# Crpto01JTAG.net
KiCad netlist of a schematic drawn in Altium Designer
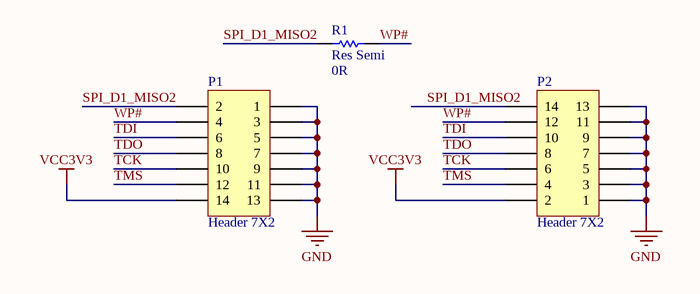
[diagram p0: Crpto01JTAG.SchDoc]

(export (version "E")
  (design (tool "Eeschema 10.0.6"))
  (components
    (comp (ref "P1")
      (value "Header 7X2")
      (footprint "JTAG_WM9059CT-ND")
      (description "Header, 7-Pin, Dual row")
      (fields (field (name "PUBLISHER") "Altium Limited"))
      (libsource (lib "") (part "Header 7X2_1"))
    )
    (comp (ref "P2")
      (value "Header 7X2")
      (footprint "2x7_2.0mm_Header")
      (description "Header, 7-Pin, Dual row")
      (fields (field (name "PUBLISHER") "Altium Limited"))
      (libsource (lib "Miscellaneous Connectors") (part "Header 7X2"))
    )
    (comp (ref "R1")
      (value "Res Semi")
      (footprint "0402")
      (description "Semiconductor Resistor")
      (fields (field (name "ALTIUM_VALUE") "0R") (field (name "PUBLISHER") "Altium Limited"))
      (libsource (lib "Miscellaneous Devices") (part "Res Semi"))
    )
  )
  (nets
    (net (code "1") (name "/SPI_D1_MISO2") (class "Default")
      (node (ref "P1") (pin "2") (pinfunction "2_2") (pintype "passive"))
      (node (ref "P2") (pin "14") (pinfunction "14_14") (pintype "passive"))
      (node (ref "R1") (pin "1") (pinfunction "1_1") (pintype "passive"))
    )
    (net (code "2") (name "/TCK") (class "Default")
      (node (ref "P1") (pin "10") (pinfunction "10_10") (pintype "passive"))
      (node (ref "P2") (pin "6") (pinfunction "6_6") (pintype "passive"))
    )
    (net (code "3") (name "/TDI") (class "Default")
      (node (ref "P1") (pin "6") (pinfunction "6_6") (pintype "passive"))
      (node (ref "P2") (pin "10") (pinfunction "10_10") (pintype "passive"))
    )
    (net (code "4") (name "/TDO") (class "Default")
      (node (ref "P1") (pin "8") (pinfunction "8_8") (pintype "passive"))
      (node (ref "P2") (pin "8") (pinfunction "8_8") (pintype "passive"))
    )
    (net (code "5") (name "/TMS") (class "Default")
      (node (ref "P1") (pin "12") (pinfunction "12_12") (pintype "passive"))
      (node (ref "P2") (pin "4") (pinfunction "4_4") (pintype "passive"))
    )
    (net (code "6") (name "/WP#") (class "Default")
      (node (ref "P1") (pin "4") (pinfunction "4_4") (pintype "passive"))
      (node (ref "P2") (pin "12") (pinfunction "12_12") (pintype "passive"))
      (node (ref "R1") (pin "2") (pinfunction "2_2") (pintype "passive"))
    )
    (net (code "7") (name "GND") (class "Default")
      (node (ref "P1") (pin "1") (pinfunction "1_1") (pintype "passive"))
      (node (ref "P1") (pin "11") (pinfunction "11_11") (pintype "passive"))
      (node (ref "P1") (pin "13") (pinfunction "13_13") (pintype "passive"))
      (node (ref "P1") (pin "3") (pinfunction "3_3") (pintype "passive"))
      (node (ref "P1") (pin "5") (pinfunction "5_5") (pintype "passive"))
      (node (ref "P1") (pin "7") (pinfunction "7_7") (pintype "passive"))
      (node (ref "P1") (pin "9") (pinfunction "9_9") (pintype "passive"))
      (node (ref "P2") (pin "1") (pinfunction "1_1") (pintype "passive"))
      (node (ref "P2") (pin "11") (pinfunction "11_11") (pintype "passive"))
      (node (ref "P2") (pin "13") (pinfunction "13_13") (pintype "passive"))
      (node (ref "P2") (pin "3") (pinfunction "3_3") (pintype "passive"))
      (node (ref "P2") (pin "5") (pinfunction "5_5") (pintype "passive"))
      (node (ref "P2") (pin "7") (pinfunction "7_7") (pintype "passive"))
      (node (ref "P2") (pin "9") (pinfunction "9_9") (pintype "passive"))
    )
    (net (code "8") (name "VCC3V3") (class "Default")
      (node (ref "P1") (pin "14") (pinfunction "14_14") (pintype "passive"))
      (node (ref "P2") (pin "2") (pinfunction "2_2") (pintype "passive"))
    )
  )
)
